# ADSB_Filter_LNA_v3.net
KiCad netlist of a schematic drawn in EAGLE
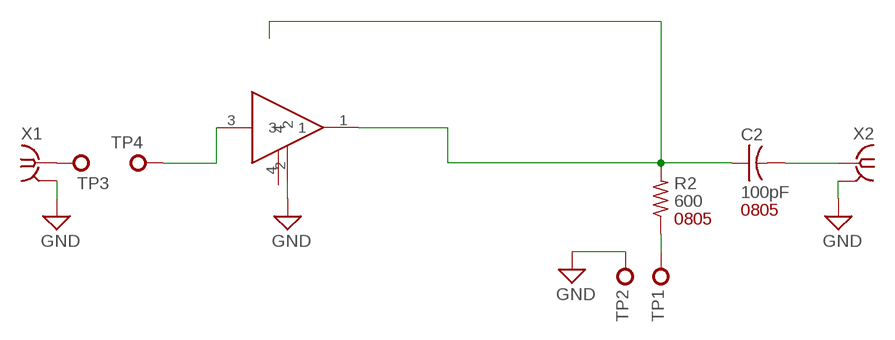
[diagram p0: schematic, sheet 1]

(export (version "E")
  (design (tool "Eeschema 10.0.6"))
  (components
    (comp (ref "C2")
      (value "100pF")
      (footprint "eagle-import:0805")
      (libsource (lib "eagle-import") (part "CAP0805"))
    )
    (comp (ref "R2")
      (value "600")
      (footprint "eagle-import:0805")
      (libsource (lib "eagle-import") (part "RES0805"))
    )
    (comp (ref "TP1")
      (value "TEST_POINTS76_150")
      (footprint "eagle-import:SMD_76_150")
      (libsource (lib "eagle-import") (part "TEST_POINTS76_150"))
    )
    (comp (ref "TP2")
      (value "TEST_POINTS76_150")
      (footprint "eagle-import:SMD_76_150")
      (libsource (lib "eagle-import") (part "TEST_POINTS76_150"))
    )
    (comp (ref "TP3")
      (value "TEST_POINTS8_8")
      (footprint "eagle-import:SMD_8_8")
      (libsource (lib "eagle-import") (part "TEST_POINTS8_8"))
    )
    (comp (ref "TP4")
      (value "TEST_POINTS8_8")
      (footprint "eagle-import:SMD_8_8")
      (libsource (lib "eagle-import") (part "TEST_POINTS8_8"))
    )
    (comp (ref "U$1")
      (value "SPF-5043Z")
      (footprint "eagle-import:SOT-343_2&4_FUSED")
      (libsource (lib "eagle-import") (part "SPF-5043Z"))
    )
    (comp (ref "X1")
      (value "SMA-142-0701-801/806")
      (footprint "eagle-import:J502-ND-142-0701-801_806")
      (fields (field (name "MF") "JOHNSON COMPONENTS") (field (name "MPN") "142-0701-801"))
      (libsource (lib "eagle-import") (part "SMA-142-0701-801/806"))
    )
    (comp (ref "X2")
      (value "SMA-142-0701-801/806")
      (footprint "eagle-import:J502-ND-142-0701-801_806")
      (fields (field (name "MF") "JOHNSON COMPONENTS") (field (name "MPN") "142-0701-801"))
      (libsource (lib "eagle-import") (part "SMA-142-0701-801/806"))
    )
  )
  (nets
    (net (code "1") (name "GND") (class "Default")
      (node (ref "TP2") (pin "1") (pinfunction "MP_1") (pintype "passive"))
      (node (ref "U$1") (pin "2") (pinfunction "2_2") (pintype "bidirectional"))
      (node (ref "X1") (pin "G@1") (pinfunction "GND_G@1") (pintype "power_in"))
      (node (ref "X2") (pin "G@1") (pinfunction "GND_G@1") (pintype "power_in"))
    )
    (net (code "2") (name "Net-(C2-Pad1)") (class "Default")
      (node (ref "C2") (pin "1") (pinfunction "1_1") (pintype "passive"))
      (node (ref "R2") (pin "2") (pinfunction "2_2") (pintype "passive"))
      (node (ref "U$1") (pin "1") (pinfunction "1_1") (pintype "bidirectional"))
    )
    (net (code "3") (name "Net-(C2-Pad2)") (class "Default")
      (node (ref "C2") (pin "2") (pinfunction "2_2") (pintype "passive"))
      (node (ref "X2") (pin "1") (pinfunction "1_1") (pintype "passive"))
    )
    (net (code "4") (name "Net-(TP1-MP)") (class "Default")
      (node (ref "R2") (pin "1") (pinfunction "1_1") (pintype "passive"))
      (node (ref "TP1") (pin "1") (pinfunction "MP_1") (pintype "passive"))
    )
    (net (code "5") (name "Net-(TP3-MP)") (class "Default")
      (node (ref "TP3") (pin "1") (pinfunction "MP_1") (pintype "passive"))
      (node (ref "X1") (pin "1") (pinfunction "1_1") (pintype "passive"))
    )
    (net (code "6") (name "Net-(TP4-MP)") (class "Default")
      (node (ref "TP4") (pin "1") (pinfunction "MP_1") (pintype "passive"))
      (node (ref "U$1") (pin "3") (pinfunction "3_3") (pintype "bidirectional"))
    )
    (net (code "7") (name "unconnected-(U$1-Pad4)") (class "Default")
      (node (ref "U$1") (pin "4") (pinfunction "4_4") (pintype "bidirectional"))
    )
  )
)
